# si4844.net
KiCad netlist of a schematic drawn in EAGLE
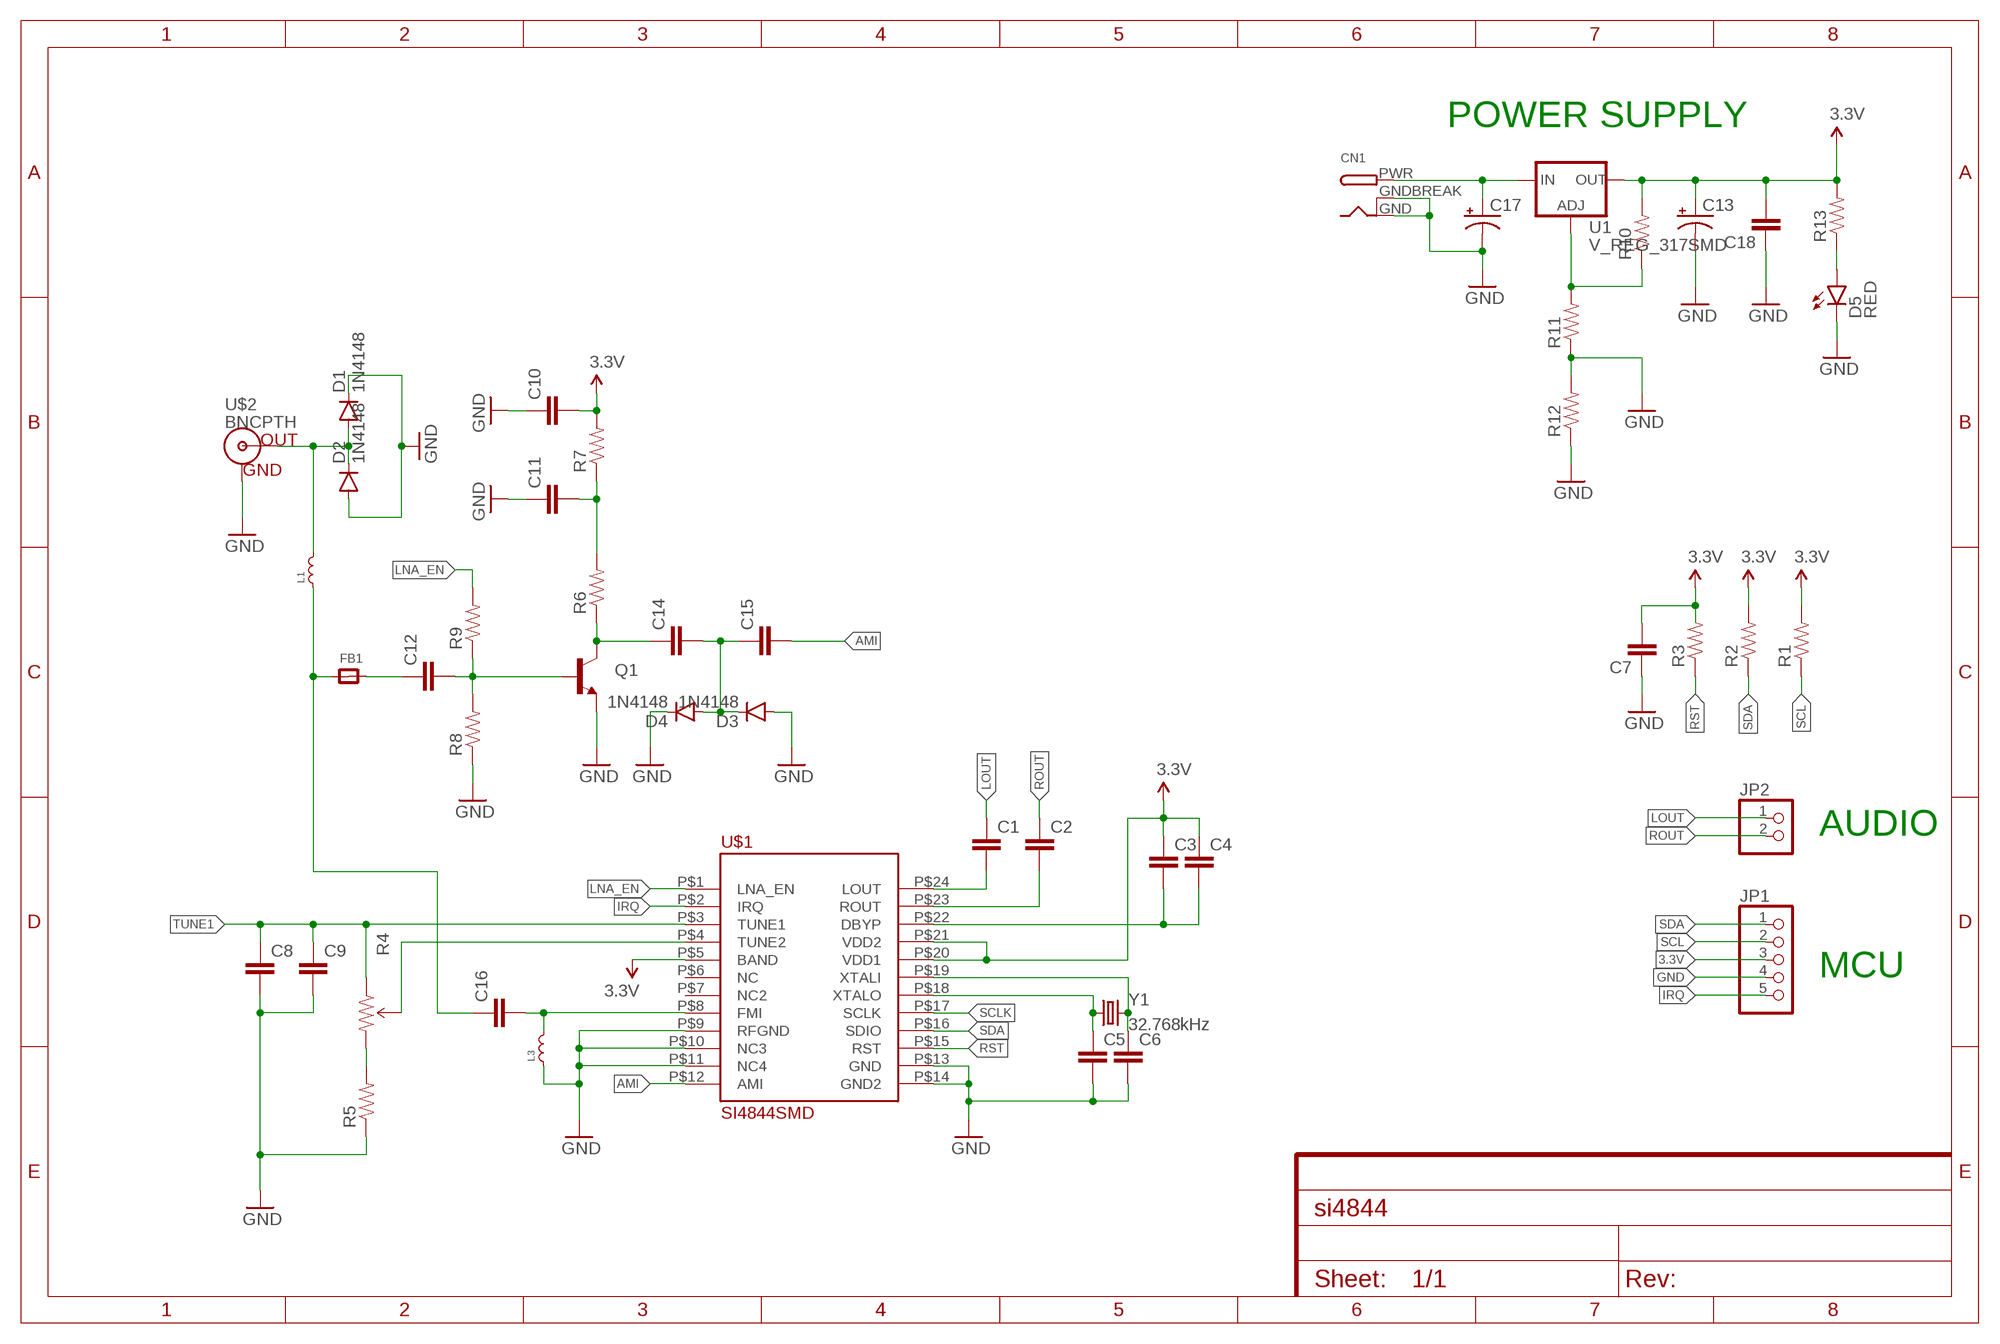
[diagram p0: schematic, sheet 1]

(export (version "E")
  (design (tool "Eeschema 10.0.6"))
  (components
    (comp (ref "C1")
      (value "CAP0603-CAP")
      (footprint "eagle-import:0603-CAP")
      (libsource (lib "eagle-import") (part "CAP0603-CAP"))
    )
    (comp (ref "C2")
      (value "CAP0603-CAP")
      (footprint "eagle-import:0603-CAP")
      (libsource (lib "eagle-import") (part "CAP0603-CAP"))
    )
    (comp (ref "C3")
      (value "CAP0603-CAP")
      (footprint "eagle-import:0603-CAP")
      (libsource (lib "eagle-import") (part "CAP0603-CAP"))
    )
    (comp (ref "C4")
      (value "CAP0603-CAP")
      (footprint "eagle-import:0603-CAP")
      (libsource (lib "eagle-import") (part "CAP0603-CAP"))
    )
    (comp (ref "C5")
      (value "CAP0603-CAP")
      (footprint "eagle-import:0603-CAP")
      (libsource (lib "eagle-import") (part "CAP0603-CAP"))
    )
    (comp (ref "C6")
      (value "CAP0603-CAP")
      (footprint "eagle-import:0603-CAP")
      (libsource (lib "eagle-import") (part "CAP0603-CAP"))
    )
    (comp (ref "C7")
      (value "CAP0603-CAP")
      (footprint "eagle-import:0603-CAP")
      (libsource (lib "eagle-import") (part "CAP0603-CAP"))
    )
    (comp (ref "C8")
      (value "CAP0603-CAP")
      (footprint "eagle-import:0603-CAP")
      (libsource (lib "eagle-import") (part "CAP0603-CAP"))
    )
    (comp (ref "C9")
      (value "CAP0603-CAP")
      (footprint "eagle-import:0603-CAP")
      (libsource (lib "eagle-import") (part "CAP0603-CAP"))
    )
    (comp (ref "C10")
      (value "CAP0603-CAP")
      (footprint "eagle-import:0603-CAP")
      (libsource (lib "eagle-import") (part "CAP0603-CAP"))
    )
    (comp (ref "C11")
      (value "CAP0603-CAP")
      (footprint "eagle-import:0603-CAP")
      (libsource (lib "eagle-import") (part "CAP0603-CAP"))
    )
    (comp (ref "C12")
      (value "CAP0603-CAP")
      (footprint "eagle-import:0603-CAP")
      (libsource (lib "eagle-import") (part "CAP0603-CAP"))
    )
    (comp (ref "C13")
      (value "CAP_POL1206-KIT")
      (footprint "eagle-import:EIA3216-KIT")
      (libsource (lib "eagle-import") (part "CAP_POL1206-KIT"))
    )
    (comp (ref "C14")
      (value "CAP0603-CAP")
      (footprint "eagle-import:0603-CAP")
      (libsource (lib "eagle-import") (part "CAP0603-CAP"))
    )
    (comp (ref "C15")
      (value "CAP0603-CAP")
      (footprint "eagle-import:0603-CAP")
      (libsource (lib "eagle-import") (part "CAP0603-CAP"))
    )
    (comp (ref "C16")
      (value "CAP0603-CAP")
      (footprint "eagle-import:0603-CAP")
      (libsource (lib "eagle-import") (part "CAP0603-CAP"))
    )
    (comp (ref "C17")
      (value "CAP_POL1206-KIT")
      (footprint "eagle-import:EIA3216-KIT")
      (libsource (lib "eagle-import") (part "CAP_POL1206-KIT"))
    )
    (comp (ref "C18")
      (value "CAP0603-CAP")
      (footprint "eagle-import:0603-CAP")
      (libsource (lib "eagle-import") (part "CAP0603-CAP"))
    )
    (comp (ref "CN1")
      (value "DCBARRELPTH")
      (footprint "eagle-import:DCJACK_2MM_PTH")
      (libsource (lib "eagle-import") (part "DCBARRELPTH"))
    )
    (comp (ref "D1")
      (value "1N4148")
      (footprint "eagle-import:DIODE-1N4148")
      (libsource (lib "eagle-import") (part "DIODE1N4148"))
    )
    (comp (ref "D2")
      (value "1N4148")
      (footprint "eagle-import:DIODE-1N4148")
      (libsource (lib "eagle-import") (part "DIODE1N4148"))
    )
    (comp (ref "D3")
      (value "1N4148")
      (footprint "eagle-import:DIODE-1N4148")
      (libsource (lib "eagle-import") (part "DIODE1N4148"))
    )
    (comp (ref "D4")
      (value "1N4148")
      (footprint "eagle-import:DIODE-1N4148")
      (libsource (lib "eagle-import") (part "DIODE1N4148"))
    )
    (comp (ref "D5")
      (value "RED")
      (footprint "eagle-import:LED-1206")
      (libsource (lib "eagle-import") (part "LED-RED1206"))
    )
    (comp (ref "FB1")
      (value "FERRITE_0603")
      (footprint "eagle-import:_0603")
      (libsource (lib "eagle-import") (part "FERRITE_0603"))
    )
    (comp (ref "JP1")
      (value "HEADER-1X5")
      (footprint "eagle-import:1X05_OVAL")
      (libsource (lib "eagle-import") (part "HEADER-1X5"))
    )
    (comp (ref "JP2")
      (value "HEADER-1X2")
      (footprint "eagle-import:1X02_OVAL")
      (libsource (lib "eagle-import") (part "HEADER-1X2"))
    )
    (comp (ref "L1")
      (value "RF-INDUCTOR.0603")
      (footprint "eagle-import:0603")
      (libsource (lib "eagle-import") (part "RF-INDUCTOR.0603"))
    )
    (comp (ref "L3")
      (value "RF-INDUCTOR.0603")
      (footprint "eagle-import:0603")
      (libsource (lib "eagle-import") (part "RF-INDUCTOR.0603"))
    )
    (comp (ref "Q1")
      (value "TRANSISTOR_NPNBC547")
      (footprint "eagle-import:TO-92-AMMO")
      (libsource (lib "eagle-import") (part "TRANSISTOR_NPNBC547"))
    )
    (comp (ref "R1")
      (value "RESISTOR0603-RES")
      (footprint "eagle-import:0603-RES")
      (libsource (lib "eagle-import") (part "RESISTOR0603-RES"))
    )
    (comp (ref "R2")
      (value "RESISTOR0603-RES")
      (footprint "eagle-import:0603-RES")
      (libsource (lib "eagle-import") (part "RESISTOR0603-RES"))
    )
    (comp (ref "R3")
      (value "RESISTOR0603-RES")
      (footprint "eagle-import:0603-RES")
      (libsource (lib "eagle-import") (part "RESISTOR0603-RES"))
    )
    (comp (ref "R4")
      (value "TRIMPOT3362U-2")
      (footprint "eagle-import:3362U-2")
      (libsource (lib "eagle-import") (part "TRIMPOT3362U-2"))
    )
    (comp (ref "R5")
      (value "RESISTOR0603-RES")
      (footprint "eagle-import:0603-RES")
      (libsource (lib "eagle-import") (part "RESISTOR0603-RES"))
    )
    (comp (ref "R6")
      (value "RESISTOR0603-RES")
      (footprint "eagle-import:0603-RES")
      (libsource (lib "eagle-import") (part "RESISTOR0603-RES"))
    )
    (comp (ref "R7")
      (value "RESISTOR0603-RES")
      (footprint "eagle-import:0603-RES")
      (libsource (lib "eagle-import") (part "RESISTOR0603-RES"))
    )
    (comp (ref "R8")
      (value "RESISTOR0603-RES")
      (footprint "eagle-import:0603-RES")
      (libsource (lib "eagle-import") (part "RESISTOR0603-RES"))
    )
    (comp (ref "R9")
      (value "RESISTOR0603-RES")
      (footprint "eagle-import:0603-RES")
      (libsource (lib "eagle-import") (part "RESISTOR0603-RES"))
    )
    (comp (ref "R10")
      (value "RESISTOR0603-RES")
      (footprint "eagle-import:0603-RES")
      (libsource (lib "eagle-import") (part "RESISTOR0603-RES"))
    )
    (comp (ref "R11")
      (value "RESISTOR0603-RES")
      (footprint "eagle-import:0603-RES")
      (libsource (lib "eagle-import") (part "RESISTOR0603-RES"))
    )
    (comp (ref "R12")
      (value "RESISTOR0603-RES")
      (footprint "eagle-import:0603-RES")
      (libsource (lib "eagle-import") (part "RESISTOR0603-RES"))
    )
    (comp (ref "R13")
      (value "RESISTOR0603-RES")
      (footprint "eagle-import:0603-RES")
      (libsource (lib "eagle-import") (part "RESISTOR0603-RES"))
    )
    (comp (ref "U$1")
      (value "SI4844SMD")
      (footprint "eagle-import:SSOP24")
      (libsource (lib "eagle-import") (part "SI4844SMD"))
    )
    (comp (ref "U$2")
      (value "BNCPTH")
      (footprint "eagle-import:BNC")
      (libsource (lib "eagle-import") (part "BNCPTH"))
    )
    (comp (ref "U1")
      (value "V_REG_317SMD")
      (footprint "eagle-import:SOT223")
      (libsource (lib "eagle-import") (part "V_REG_317SMD"))
    )
    (comp (ref "Y1")
      (value "32.768kHz")
      (footprint "eagle-import:CRYSTAL-SMD-3.2X1.5MM")
      (libsource (lib "eagle-import") (part "CRYSTAL3.2X1.5MM"))
    )
  )
  (nets
    (net (code "1") (name "3.3V") (class "Default")
      (node (ref "C10") (pin "2") (pinfunction "2_2") (pintype "passive"))
      (node (ref "C13") (pin "A") (pinfunction "+_A") (pintype "passive"))
      (node (ref "C18") (pin "2") (pinfunction "2_2") (pintype "passive"))
      (node (ref "C3") (pin "1") (pinfunction "1_1") (pintype "passive"))
      (node (ref "C4") (pin "1") (pinfunction "1_1") (pintype "passive"))
      (node (ref "C7") (pin "2") (pinfunction "2_2") (pintype "passive"))
      (node (ref "JP1") (pin "3") (pinfunction "3_3") (pintype "passive"))
      (node (ref "R1") (pin "2") (pinfunction "2_2") (pintype "passive"))
      (node (ref "R10") (pin "2") (pinfunction "2_2") (pintype "passive"))
      (node (ref "R13") (pin "2") (pinfunction "2_2") (pintype "passive"))
      (node (ref "R2") (pin "2") (pinfunction "2_2") (pintype "passive"))
      (node (ref "R3") (pin "2") (pinfunction "2_2") (pintype "passive"))
      (node (ref "R7") (pin "2") (pinfunction "2_2") (pintype "passive"))
      (node (ref "U$1") (pin "P$20") (pinfunction "VDD1_P$20") (pintype "bidirectional"))
      (node (ref "U$1") (pin "P$21") (pinfunction "VDD2_P$21") (pintype "bidirectional"))
      (node (ref "U$1") (pin "P$5") (pinfunction "BAND_P$5") (pintype "bidirectional"))
      (node (ref "U1") (pin "2") (pinfunction "OUT_2") (pintype "output"))
    )
    (net (code "2") (name "AMI") (class "Default")
      (node (ref "C15") (pin "2") (pinfunction "2_2") (pintype "passive"))
      (node (ref "U$1") (pin "P$12") (pinfunction "AMI_P$12") (pintype "bidirectional"))
    )
    (net (code "3") (name "GND") (class "Default")
      (node (ref "C10") (pin "1") (pinfunction "1_1") (pintype "passive"))
      (node (ref "C11") (pin "1") (pinfunction "1_1") (pintype "passive"))
      (node (ref "C13") (pin "C") (pinfunction "-_C") (pintype "passive"))
      (node (ref "C17") (pin "C") (pinfunction "-_C") (pintype "passive"))
      (node (ref "C18") (pin "1") (pinfunction "1_1") (pintype "passive"))
      (node (ref "C5") (pin "2") (pinfunction "2_2") (pintype "passive"))
      (node (ref "C6") (pin "2") (pinfunction "2_2") (pintype "passive"))
      (node (ref "C7") (pin "1") (pinfunction "1_1") (pintype "passive"))
      (node (ref "C8") (pin "2") (pinfunction "2_2") (pintype "passive"))
      (node (ref "C9") (pin "2") (pinfunction "2_2") (pintype "passive"))
      (node (ref "CN1") (pin "GND") (pinfunction "GND_GND") (pintype "power_in"))
      (node (ref "CN1") (pin "GNDBREAK") (pinfunction "GNDBREAK_GNDBREAK") (pintype "power_in"))
      (node (ref "D1") (pin "C") (pinfunction "C_C") (pintype "passive"))
      (node (ref "D2") (pin "A") (pinfunction "A_A") (pintype "passive"))
      (node (ref "D3") (pin "A") (pinfunction "A_A") (pintype "passive"))
      (node (ref "D4") (pin "C") (pinfunction "C_C") (pintype "passive"))
      (node (ref "D5") (pin "C") (pinfunction "C_C") (pintype "passive"))
      (node (ref "JP1") (pin "4") (pinfunction "4_4") (pintype "passive"))
      (node (ref "L3") (pin "1") (pinfunction "1_1") (pintype "passive"))
      (node (ref "Q1") (pin "3") (pinfunction "E_3") (pintype "passive"))
      (node (ref "R11") (pin "1") (pinfunction "1_1") (pintype "passive"))
      (node (ref "R12") (pin "1") (pinfunction "1_1") (pintype "passive"))
      (node (ref "R12") (pin "2") (pinfunction "2_2") (pintype "passive"))
      (node (ref "R5") (pin "1") (pinfunction "1_1") (pintype "passive"))
      (node (ref "R8") (pin "1") (pinfunction "1_1") (pintype "passive"))
      (node (ref "U$1") (pin "P$10") (pinfunction "NC3_P$10") (pintype "bidirectional"))
      (node (ref "U$1") (pin "P$11") (pinfunction "NC4_P$11") (pintype "bidirectional"))
      (node (ref "U$1") (pin "P$13") (pinfunction "GND_P$13") (pintype "bidirectional"))
      (node (ref "U$1") (pin "P$14") (pinfunction "GND2_P$14") (pintype "bidirectional"))
      (node (ref "U$1") (pin "P$9") (pinfunction "RFGND_P$9") (pintype "bidirectional"))
      (node (ref "U$2") (pin "GND") (pinfunction "GND_GND") (pintype "bidirectional"))
    )
    (net (code "4") (name "IRQ") (class "Default")
      (node (ref "JP1") (pin "5") (pinfunction "5_5") (pintype "passive"))
      (node (ref "U$1") (pin "P$2") (pinfunction "IRQ_P$2") (pintype "bidirectional"))
    )
    (net (code "5") (name "LNA_EN") (class "Default")
      (node (ref "R9") (pin "2") (pinfunction "2_2") (pintype "passive"))
      (node (ref "U$1") (pin "P$1") (pinfunction "LNA_EN_P$1") (pintype "bidirectional"))
    )
    (net (code "6") (name "LOUT") (class "Default")
      (node (ref "C1") (pin "1") (pinfunction "1_1") (pintype "passive"))
      (node (ref "JP2") (pin "1") (pinfunction "1_1") (pintype "passive"))
    )
    (net (code "7") (name "Net-(C11-Pad2)") (class "Default")
      (node (ref "C11") (pin "2") (pinfunction "2_2") (pintype "passive"))
      (node (ref "R6") (pin "2") (pinfunction "2_2") (pintype "passive"))
      (node (ref "R7") (pin "1") (pinfunction "1_1") (pintype "passive"))
    )
    (net (code "8") (name "Net-(C14-Pad2)") (class "Default")
      (node (ref "C14") (pin "2") (pinfunction "2_2") (pintype "passive"))
      (node (ref "C15") (pin "1") (pinfunction "1_1") (pintype "passive"))
      (node (ref "D3") (pin "C") (pinfunction "C_C") (pintype "passive"))
      (node (ref "D4") (pin "A") (pinfunction "A_A") (pintype "passive"))
    )
    (net (code "9") (name "Net-(C17-+)") (class "Default")
      (node (ref "C17") (pin "A") (pinfunction "+_A") (pintype "passive"))
      (node (ref "CN1") (pin "PWR") (pinfunction "PWR_PWR") (pintype "power_in"))
      (node (ref "U1") (pin "3") (pinfunction "IN_3") (pintype "input"))
    )
    (net (code "10") (name "Net-(D5-PadA)") (class "Default")
      (node (ref "D5") (pin "A") (pinfunction "A_A") (pintype "passive"))
      (node (ref "R13") (pin "1") (pinfunction "1_1") (pintype "passive"))
    )
    (net (code "11") (name "Net-(FB1-P$1)") (class "Default")
      (node (ref "C16") (pin "1") (pinfunction "1_1") (pintype "passive"))
      (node (ref "FB1") (pin "1") (pinfunction "P$1_1") (pintype "passive"))
      (node (ref "L1") (pin "1") (pinfunction "1_1") (pintype "passive"))
    )
    (net (code "12") (name "Net-(FB1-P$2)") (class "Default")
      (node (ref "C12") (pin "1") (pinfunction "1_1") (pintype "passive"))
      (node (ref "FB1") (pin "2") (pinfunction "P$2_2") (pintype "passive"))
    )
    (net (code "13") (name "Net-(Q1-B)") (class "Default")
      (node (ref "C12") (pin "2") (pinfunction "2_2") (pintype "passive"))
      (node (ref "Q1") (pin "2") (pinfunction "B_2") (pintype "passive"))
      (node (ref "R8") (pin "2") (pinfunction "2_2") (pintype "passive"))
      (node (ref "R9") (pin "1") (pinfunction "1_1") (pintype "passive"))
    )
    (net (code "14") (name "Net-(Q1-C)") (class "Default")
      (node (ref "C14") (pin "1") (pinfunction "1_1") (pintype "passive"))
      (node (ref "Q1") (pin "1") (pinfunction "C_1") (pintype "passive"))
      (node (ref "R6") (pin "1") (pinfunction "1_1") (pintype "passive"))
    )
    (net (code "15") (name "Net-(R4-CW)") (class "Default")
      (node (ref "R4") (pin "3") (pinfunction "CW_3") (pintype "passive"))
      (node (ref "R5") (pin "2") (pinfunction "2_2") (pintype "passive"))
    )
    (net (code "16") (name "Net-(R4-WIPER)") (class "Default")
      (node (ref "R4") (pin "2") (pinfunction "WIPER_2") (pintype "passive"))
      (node (ref "U$1") (pin "P$4") (pinfunction "TUNE2_P$4") (pintype "bidirectional"))
    )
    (net (code "17") (name "Net-(U$1-DBYP)") (class "Default")
      (node (ref "C3") (pin "2") (pinfunction "2_2") (pintype "passive"))
      (node (ref "C4") (pin "2") (pinfunction "2_2") (pintype "passive"))
      (node (ref "U$1") (pin "P$22") (pinfunction "DBYP_P$22") (pintype "bidirectional"))
    )
    (net (code "18") (name "Net-(U$1-FMI)") (class "Default")
      (node (ref "C16") (pin "2") (pinfunction "2_2") (pintype "passive"))
      (node (ref "L3") (pin "2") (pinfunction "2_2") (pintype "passive"))
      (node (ref "U$1") (pin "P$8") (pinfunction "FMI_P$8") (pintype "bidirectional"))
    )
    (net (code "19") (name "Net-(U$1-LOUT)") (class "Default")
      (node (ref "C1") (pin "2") (pinfunction "2_2") (pintype "passive"))
      (node (ref "U$1") (pin "P$24") (pinfunction "LOUT_P$24") (pintype "bidirectional"))
    )
    (net (code "20") (name "Net-(U$1-ROUT)") (class "Default")
      (node (ref "C2") (pin "2") (pinfunction "2_2") (pintype "passive"))
      (node (ref "U$1") (pin "P$23") (pinfunction "ROUT_P$23") (pintype "bidirectional"))
    )
    (net (code "21") (name "Net-(U$1-XTALI)") (class "Default")
      (node (ref "C6") (pin "1") (pinfunction "1_1") (pintype "passive"))
      (node (ref "U$1") (pin "P$19") (pinfunction "XTALI_P$19") (pintype "bidirectional"))
      (node (ref "Y1") (pin "P$2") (pinfunction "2_P$2") (pintype "passive"))
    )
    (net (code "22") (name "Net-(U$1-XTALO)") (class "Default")
      (node (ref "C5") (pin "1") (pinfunction "1_1") (pintype "passive"))
      (node (ref "U$1") (pin "P$18") (pinfunction "XTALO_P$18") (pintype "bidirectional"))
      (node (ref "Y1") (pin "P$1") (pinfunction "1_P$1") (pintype "passive"))
    )
    (net (code "23") (name "Net-(U$2-OUT)") (class "Default")
      (node (ref "D1") (pin "A") (pinfunction "A_A") (pintype "passive"))
      (node (ref "D2") (pin "C") (pinfunction "C_C") (pintype "passive"))
      (node (ref "L1") (pin "2") (pinfunction "2_2") (pintype "passive"))
      (node (ref "U$2") (pin "S") (pinfunction "OUT_S") (pintype "bidirectional"))
    )
    (net (code "24") (name "Net-(U1-ADJ)") (class "Default")
      (node (ref "R10") (pin "1") (pinfunction "1_1") (pintype "passive"))
      (node (ref "R11") (pin "2") (pinfunction "2_2") (pintype "passive"))
      (node (ref "U1") (pin "1") (pinfunction "ADJ_1") (pintype "input"))
    )
    (net (code "25") (name "ROUT") (class "Default")
      (node (ref "C2") (pin "1") (pinfunction "1_1") (pintype "passive"))
      (node (ref "JP2") (pin "2") (pinfunction "2_2") (pintype "passive"))
    )
    (net (code "26") (name "RST") (class "Default")
      (node (ref "R3") (pin "1") (pinfunction "1_1") (pintype "passive"))
      (node (ref "U$1") (pin "P$15") (pinfunction "RST_P$15") (pintype "bidirectional"))
    )
    (net (code "27") (name "SCL") (class "Default")
      (node (ref "JP1") (pin "2") (pinfunction "2_2") (pintype "passive"))
      (node (ref "R1") (pin "1") (pinfunction "1_1") (pintype "passive"))
    )
    (net (code "28") (name "SCLK") (class "Default")
      (node (ref "U$1") (pin "P$17") (pinfunction "SCLK_P$17") (pintype "bidirectional"))
    )
    (net (code "29") (name "SDA") (class "Default")
      (node (ref "JP1") (pin "1") (pinfunction "1_1") (pintype "passive"))
      (node (ref "R2") (pin "1") (pinfunction "1_1") (pintype "passive"))
      (node (ref "U$1") (pin "P$16") (pinfunction "SDIO_P$16") (pintype "bidirectional"))
    )
    (net (code "30") (name "TUNE1") (class "Default")
      (node (ref "C8") (pin "1") (pinfunction "1_1") (pintype "passive"))
      (node (ref "C9") (pin "1") (pinfunction "1_1") (pintype "passive"))
      (node (ref "R4") (pin "1") (pinfunction "CCW_1") (pintype "passive"))
      (node (ref "U$1") (pin "P$3") (pinfunction "TUNE1_P$3") (pintype "bidirectional"))
    )
    (net (code "31") (name "unconnected-(U$1-NC-PadP$6)") (class "Default")
      (node (ref "U$1") (pin "P$6") (pinfunction "NC_P$6") (pintype "bidirectional"))
    )
    (net (code "32") (name "unconnected-(U$1-NC2-PadP$7)") (class "Default")
      (node (ref "U$1") (pin "P$7") (pinfunction "NC2_P$7") (pintype "bidirectional"))
    )
  )
)
